# Kayan22v1.net
KiCad netlist of a schematic drawn in Altium Designer
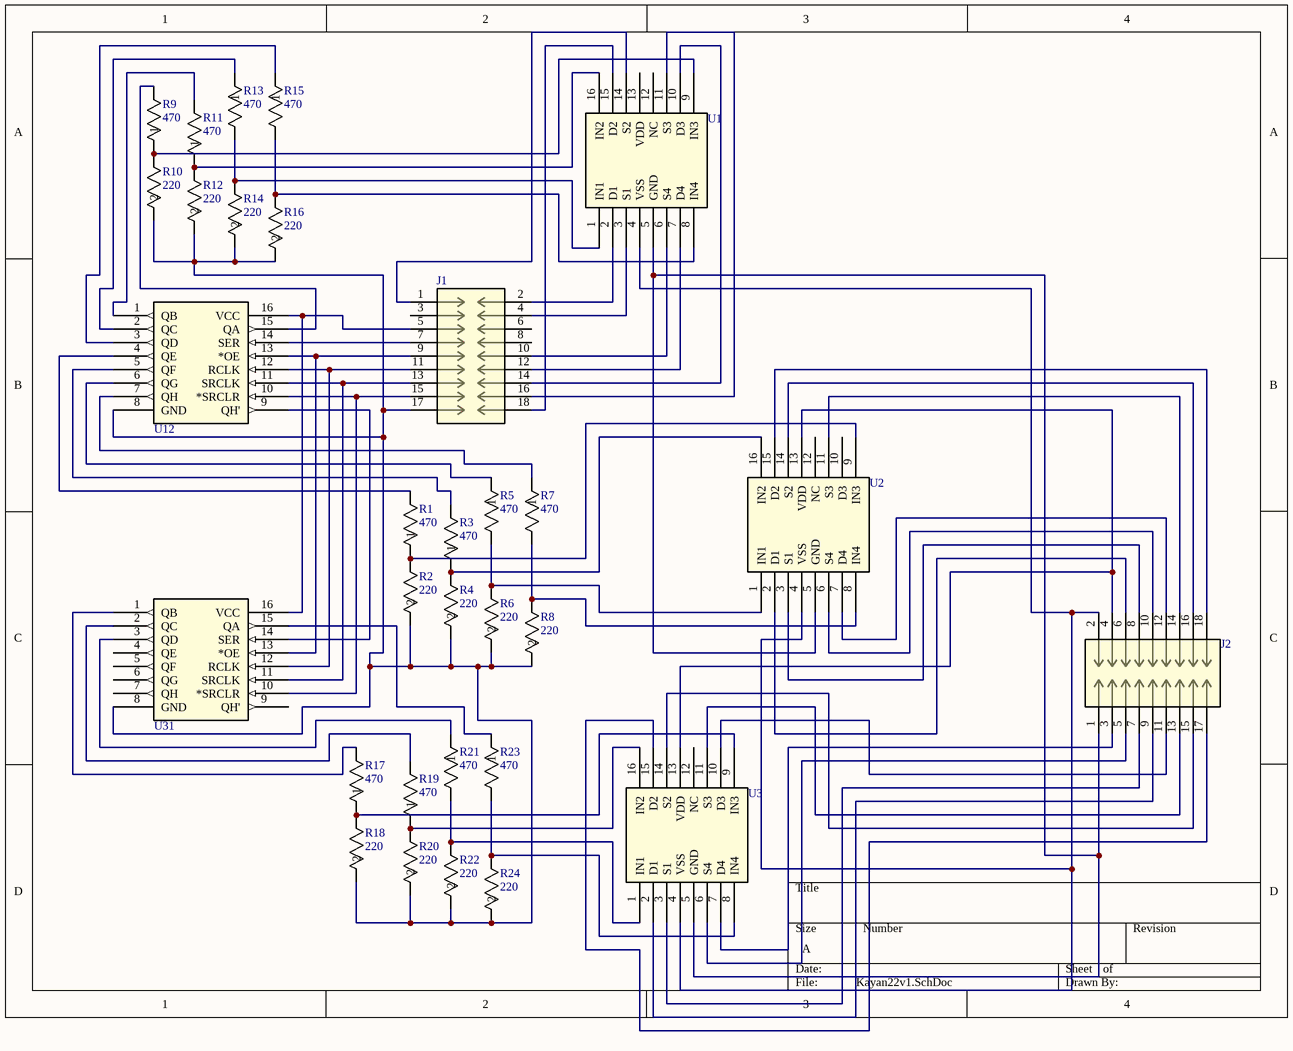
[diagram p0: Kayan22v1.SchDoc]

(export (version "E")
  (design (tool "Eeschema 10.0.6"))
  (components
    (comp (ref "J1")
      (value "68602-116HLF")
      (footprint "CONN_68602-116HLF_AMP")
      (description "No Description Available")
      (fields (field (name "COPYRIGHT") "Copyright (C) 2023 Ultra Librarian. All rights reserved."))
      (libsource (lib "68602-116HLF") (part "68602-116HLF"))
    )
    (comp (ref "J2")
      (value "68602-116HLF")
      (footprint "CONN_68602-116HLF_AMP")
      (description "No Description Available")
      (fields (field (name "COPYRIGHT") "Copyright (C) 2023 Ultra Librarian. All rights reserved."))
      (libsource (lib "68602-116HLF") (part "68602-116HLF"))
    )
    (comp (ref "R1")
      (value "470")
      (footprint "RES_ERA6V,6K_PAN")
      (description "No Description Available")
      (fields
        (field (name "MANUFACTURER_PART_NUMBER") "ERA-6VEB4700V")
        (field (name "COPYRIGHT") "Copyright (C) 2023 Ultra Librarian. All rights reserved.")
      )
      (libsource (lib "ERA-6VEB4700V") (part "ERA-6VEB4700V"))
    )
    (comp (ref "R2")
      (value "220")
      (footprint "RC0805N_PAN")
      (description "No Description Available")
      (fields
        (field (name "MANUFACTURER_PART_NUMBER") "ERA-6AEB221V")
        (field (name "COPYRIGHT") "Copyright (C) 2023 Ultra Librarian. All rights reserved.")
      )
      (libsource (lib "ERA-6AEB221V") (part "ERA-6AEB221V"))
    )
    (comp (ref "R3")
      (value "470")
      (footprint "RES_ERA6V,6K_PAN")
      (description "No Description Available")
      (fields
        (field (name "MANUFACTURER_PART_NUMBER") "ERA-6VEB4700V")
        (field (name "COPYRIGHT") "Copyright (C) 2023 Ultra Librarian. All rights reserved.")
      )
      (libsource (lib "ERA-6VEB4700V") (part "ERA-6VEB4700V"))
    )
    (comp (ref "R4")
      (value "220")
      (footprint "RC0805N_PAN")
      (description "No Description Available")
      (fields
        (field (name "MANUFACTURER_PART_NUMBER") "ERA-6AEB221V")
        (field (name "COPYRIGHT") "Copyright (C) 2023 Ultra Librarian. All rights reserved.")
      )
      (libsource (lib "ERA-6AEB221V") (part "ERA-6AEB221V"))
    )
    (comp (ref "R5")
      (value "470")
      (footprint "RES_ERA6V,6K_PAN")
      (description "No Description Available")
      (fields
        (field (name "MANUFACTURER_PART_NUMBER") "ERA-6VEB4700V")
        (field (name "COPYRIGHT") "Copyright (C) 2023 Ultra Librarian. All rights reserved.")
      )
      (libsource (lib "ERA-6VEB4700V") (part "ERA-6VEB4700V"))
    )
    (comp (ref "R6")
      (value "220")
      (footprint "RC0805N_PAN")
      (description "No Description Available")
      (fields
        (field (name "MANUFACTURER_PART_NUMBER") "ERA-6AEB221V")
        (field (name "COPYRIGHT") "Copyright (C) 2023 Ultra Librarian. All rights reserved.")
      )
      (libsource (lib "ERA-6AEB221V") (part "ERA-6AEB221V"))
    )
    (comp (ref "R7")
      (value "470")
      (footprint "RES_ERA6V,6K_PAN")
      (description "No Description Available")
      (fields
        (field (name "MANUFACTURER_PART_NUMBER") "ERA-6VEB4700V")
        (field (name "COPYRIGHT") "Copyright (C) 2023 Ultra Librarian. All rights reserved.")
      )
      (libsource (lib "ERA-6VEB4700V") (part "ERA-6VEB4700V"))
    )
    (comp (ref "R8")
      (value "220")
      (footprint "RC0805N_PAN")
      (description "No Description Available")
      (fields
        (field (name "MANUFACTURER_PART_NUMBER") "ERA-6AEB221V")
        (field (name "COPYRIGHT") "Copyright (C) 2023 Ultra Librarian. All rights reserved.")
      )
      (libsource (lib "ERA-6AEB221V") (part "ERA-6AEB221V"))
    )
    (comp (ref "R9")
      (value "470")
      (footprint "RES_ERA6V,6K_PAN")
      (description "No Description Available")
      (fields
        (field (name "MANUFACTURER_PART_NUMBER") "ERA-6VEB4700V")
        (field (name "COPYRIGHT") "Copyright (C) 2023 Ultra Librarian. All rights reserved.")
      )
      (libsource (lib "ERA-6VEB4700V") (part "ERA-6VEB4700V"))
    )
    (comp (ref "R10")
      (value "220")
      (footprint "RC0805N_PAN")
      (description "No Description Available")
      (fields
        (field (name "MANUFACTURER_PART_NUMBER") "ERA-6AEB221V")
        (field (name "COPYRIGHT") "Copyright (C) 2023 Ultra Librarian. All rights reserved.")
      )
      (libsource (lib "ERA-6AEB221V") (part "ERA-6AEB221V"))
    )
    (comp (ref "R11")
      (value "470")
      (footprint "RES_ERA6V,6K_PAN")
      (description "No Description Available")
      (fields
        (field (name "MANUFACTURER_PART_NUMBER") "ERA-6VEB4700V")
        (field (name "COPYRIGHT") "Copyright (C) 2023 Ultra Librarian. All rights reserved.")
      )
      (libsource (lib "ERA-6VEB4700V") (part "ERA-6VEB4700V"))
    )
    (comp (ref "R12")
      (value "220")
      (footprint "RC0805N_PAN")
      (description "No Description Available")
      (fields
        (field (name "MANUFACTURER_PART_NUMBER") "ERA-6AEB221V")
        (field (name "COPYRIGHT") "Copyright (C) 2023 Ultra Librarian. All rights reserved.")
      )
      (libsource (lib "ERA-6AEB221V") (part "ERA-6AEB221V"))
    )
    (comp (ref "R13")
      (value "470")
      (footprint "RES_ERA6V,6K_PAN")
      (description "No Description Available")
      (fields
        (field (name "MANUFACTURER_PART_NUMBER") "ERA-6VEB4700V")
        (field (name "COPYRIGHT") "Copyright (C) 2023 Ultra Librarian. All rights reserved.")
      )
      (libsource (lib "ERA-6VEB4700V") (part "ERA-6VEB4700V"))
    )
    (comp (ref "R14")
      (value "220")
      (footprint "RC0805N_PAN")
      (description "No Description Available")
      (fields
        (field (name "MANUFACTURER_PART_NUMBER") "ERA-6AEB221V")
        (field (name "COPYRIGHT") "Copyright (C) 2023 Ultra Librarian. All rights reserved.")
      )
      (libsource (lib "ERA-6AEB221V") (part "ERA-6AEB221V"))
    )
    (comp (ref "R15")
      (value "470")
      (footprint "RES_ERA6V,6K_PAN")
      (description "No Description Available")
      (fields
        (field (name "MANUFACTURER_PART_NUMBER") "ERA-6VEB4700V")
        (field (name "COPYRIGHT") "Copyright (C) 2023 Ultra Librarian. All rights reserved.")
      )
      (libsource (lib "ERA-6VEB4700V") (part "ERA-6VEB4700V"))
    )
    (comp (ref "R16")
      (value "220")
      (footprint "RC0805N_PAN")
      (description "No Description Available")
      (fields
        (field (name "MANUFACTURER_PART_NUMBER") "ERA-6AEB221V")
        (field (name "COPYRIGHT") "Copyright (C) 2023 Ultra Librarian. All rights reserved.")
      )
      (libsource (lib "ERA-6AEB221V") (part "ERA-6AEB221V"))
    )
    (comp (ref "R17")
      (value "470")
      (footprint "RES_ERA6V,6K_PAN")
      (description "No Description Available")
      (fields
        (field (name "MANUFACTURER_PART_NUMBER") "ERA-6VEB4700V")
        (field (name "COPYRIGHT") "Copyright (C) 2023 Ultra Librarian. All rights reserved.")
      )
      (libsource (lib "ERA-6VEB4700V") (part "ERA-6VEB4700V"))
    )
    (comp (ref "R18")
      (value "220")
      (footprint "RC0805N_PAN")
      (description "No Description Available")
      (fields
        (field (name "MANUFACTURER_PART_NUMBER") "ERA-6AEB221V")
        (field (name "COPYRIGHT") "Copyright (C) 2023 Ultra Librarian. All rights reserved.")
      )
      (libsource (lib "ERA-6AEB221V") (part "ERA-6AEB221V"))
    )
    (comp (ref "R19")
      (value "470")
      (footprint "RES_ERA6V,6K_PAN")
      (description "No Description Available")
      (fields
        (field (name "MANUFACTURER_PART_NUMBER") "ERA-6VEB4700V")
        (field (name "COPYRIGHT") "Copyright (C) 2023 Ultra Librarian. All rights reserved.")
      )
      (libsource (lib "ERA-6VEB4700V") (part "ERA-6VEB4700V"))
    )
    (comp (ref "R20")
      (value "220")
      (footprint "RC0805N_PAN")
      (description "No Description Available")
      (fields
        (field (name "MANUFACTURER_PART_NUMBER") "ERA-6AEB221V")
        (field (name "COPYRIGHT") "Copyright (C) 2023 Ultra Librarian. All rights reserved.")
      )
      (libsource (lib "ERA-6AEB221V") (part "ERA-6AEB221V"))
    )
    (comp (ref "R21")
      (value "470")
      (footprint "RES_ERA6V,6K_PAN")
      (description "No Description Available")
      (fields
        (field (name "MANUFACTURER_PART_NUMBER") "ERA-6VEB4700V")
        (field (name "COPYRIGHT") "Copyright (C) 2023 Ultra Librarian. All rights reserved.")
      )
      (libsource (lib "ERA-6VEB4700V") (part "ERA-6VEB4700V"))
    )
    (comp (ref "R22")
      (value "220")
      (footprint "RC0805N_PAN")
      (description "No Description Available")
      (fields
        (field (name "MANUFACTURER_PART_NUMBER") "ERA-6AEB221V")
        (field (name "COPYRIGHT") "Copyright (C) 2023 Ultra Librarian. All rights reserved.")
      )
      (libsource (lib "ERA-6AEB221V") (part "ERA-6AEB221V"))
    )
    (comp (ref "R23")
      (value "470")
      (footprint "RES_ERA6V,6K_PAN")
      (description "No Description Available")
      (fields
        (field (name "MANUFACTURER_PART_NUMBER") "ERA-6VEB4700V")
        (field (name "COPYRIGHT") "Copyright (C) 2023 Ultra Librarian. All rights reserved.")
      )
      (libsource (lib "ERA-6VEB4700V") (part "ERA-6VEB4700V"))
    )
    (comp (ref "R24")
      (value "220")
      (footprint "RC0805N_PAN")
      (description "No Description Available")
      (fields
        (field (name "MANUFACTURER_PART_NUMBER") "ERA-6AEB221V")
        (field (name "COPYRIGHT") "Copyright (C) 2023 Ultra Librarian. All rights reserved.")
      )
      (libsource (lib "ERA-6AEB221V") (part "ERA-6AEB221V"))
    )
    (comp (ref "U1")
      (value "ADG1412YRUZ-REEL7")
      (footprint "RU_16_ADI")
      (description "No Description Available")
      (fields (field (name "COPYRIGHT") "Copyright (C) 2023 Ultra Librarian. All rights reserved."))
      (libsource (lib "ADG1412YRUZ-REEL7") (part "ADG1412YRUZ-REEL7"))
    )
    (comp (ref "U2")
      (value "ADG1412YRUZ-REEL7")
      (footprint "RU_16_ADI")
      (description "No Description Available")
      (fields (field (name "COPYRIGHT") "Copyright (C) 2023 Ultra Librarian. All rights reserved."))
      (libsource (lib "ADG1412YRUZ-REEL7") (part "ADG1412YRUZ-REEL7"))
    )
    (comp (ref "U3")
      (value "ADG1412YRUZ-REEL7")
      (footprint "RU_16_ADI")
      (description "No Description Available")
      (fields (field (name "COPYRIGHT") "Copyright (C) 2023 Ultra Librarian. All rights reserved."))
      (libsource (lib "ADG1412YRUZ-REEL7") (part "ADG1412YRUZ-REEL7"))
    )
    (comp (ref "U12")
      (value "SN74HC595DWR")
      (footprint "DW16")
      (description "No Description Available")
      (fields (field (name "COPYRIGHT") "Copyright (C) 2023 Ultra Librarian. All rights reserved."))
      (libsource (lib "SN74HC595DWR") (part "SN74HC595DWR"))
    )
    (comp (ref "U31")
      (value "SN74HC595DWR")
      (footprint "DW16")
      (description "No Description Available")
      (fields (field (name "COPYRIGHT") "Copyright (C) 2023 Ultra Librarian. All rights reserved."))
      (libsource (lib "SN74HC595DWR") (part "SN74HC595DWR"))
    )
  )
  (nets
    (net (code "1") (name "Net-(U1-D1)") (class "Default")
      (node (ref "J1") (pin "2") (pinfunction "2_2") (pintype "passive"))
      (node (ref "U1") (pin "2") (pinfunction "D1_2") (pintype "passive"))
    )
    (net (code "2") (name "Net-(U1-D2)") (class "Default")
      (node (ref "J1") (pin "18") (pinfunction "18_18") (pintype "passive"))
      (node (ref "U1") (pin "15") (pinfunction "D2_15") (pintype "passive"))
    )
    (net (code "3") (name "Net-(U1-D3)") (class "Default")
      (node (ref "J1") (pin "14") (pinfunction "14_14") (pintype "passive"))
      (node (ref "U1") (pin "10") (pinfunction "D3_10") (pintype "passive"))
    )
    (net (code "4") (name "Net-(U1-D4)") (class "Default")
      (node (ref "J1") (pin "12") (pinfunction "12_12") (pintype "passive"))
      (node (ref "U1") (pin "7") (pinfunction "D4_7") (pintype "passive"))
    )
    (net (code "5") (name "Net-(U1-GND)") (class "Default")
      (node (ref "J2") (pin "1") (pinfunction "1_1") (pintype "passive"))
      (node (ref "U1") (pin "5") (pinfunction "GND_5") (pintype "passive"))
      (node (ref "U2") (pin "5") (pinfunction "GND_5") (pintype "passive"))
      (node (ref "U3") (pin "5") (pinfunction "GND_5") (pintype "passive"))
    )
    (net (code "6") (name "Net-(U1-IN1)") (class "Default")
      (node (ref "R13") (pin "2") (pinfunction "2_2") (pintype "passive"))
      (node (ref "R14") (pin "1") (pinfunction "1_1") (pintype "passive"))
      (node (ref "U1") (pin "1") (pinfunction "IN1_1") (pintype "passive"))
    )
    (net (code "7") (name "Net-(U1-IN2)") (class "Default")
      (node (ref "R11") (pin "1") (pinfunction "1_1") (pintype "passive"))
      (node (ref "R12") (pin "1") (pinfunction "1_1") (pintype "passive"))
      (node (ref "U1") (pin "16") (pinfunction "IN2_16") (pintype "passive"))
    )
    (net (code "8") (name "Net-(U1-IN3)") (class "Default")
      (node (ref "R10") (pin "1") (pinfunction "1_1") (pintype "passive"))
      (node (ref "R9") (pin "1") (pinfunction "1_1") (pintype "passive"))
      (node (ref "U1") (pin "9") (pinfunction "IN3_9") (pintype "passive"))
    )
    (net (code "9") (name "Net-(U1-IN4)") (class "Default")
      (node (ref "R15") (pin "2") (pinfunction "2_2") (pintype "passive"))
      (node (ref "R16") (pin "1") (pinfunction "1_1") (pintype "passive"))
      (node (ref "U1") (pin "8") (pinfunction "IN4_8") (pintype "passive"))
    )
    (net (code "10") (name "Net-(U1-S1)") (class "Default")
      (node (ref "J1") (pin "4") (pinfunction "4_4") (pintype "passive"))
      (node (ref "U1") (pin "3") (pinfunction "S1_3") (pintype "passive"))
    )
    (net (code "11") (name "Net-(U1-S2)") (class "Default")
      (node (ref "J1") (pin "1") (pinfunction "1_1") (pintype "passive"))
      (node (ref "U1") (pin "14") (pinfunction "S2_14") (pintype "passive"))
    )
    (net (code "12") (name "Net-(U1-S3)") (class "Default")
      (node (ref "J1") (pin "16") (pinfunction "16_16") (pintype "passive"))
      (node (ref "U1") (pin "11") (pinfunction "S3_11") (pintype "passive"))
    )
    (net (code "13") (name "Net-(U1-S4)") (class "Default")
      (node (ref "J1") (pin "10") (pinfunction "10_10") (pintype "passive"))
      (node (ref "U1") (pin "6") (pinfunction "S4_6") (pintype "passive"))
    )
    (net (code "14") (name "Net-(U1-VSS)") (class "Default")
      (node (ref "J2") (pin "2") (pinfunction "2_2") (pintype "passive"))
      (node (ref "U1") (pin "4") (pinfunction "VSS_4") (pintype "passive"))
      (node (ref "U2") (pin "4") (pinfunction "VSS_4") (pintype "passive"))
      (node (ref "U3") (pin "4") (pinfunction "VSS_4") (pintype "passive"))
    )
    (net (code "15") (name "Net-(U2-D1)") (class "Default")
      (node (ref "J2") (pin "6") (pinfunction "6_6") (pintype "passive"))
      (node (ref "U2") (pin "2") (pinfunction "D1_2") (pintype "passive"))
    )
    (net (code "16") (name "Net-(U2-D2)") (class "Default")
      (node (ref "J2") (pin "18") (pinfunction "18_18") (pintype "passive"))
      (node (ref "U2") (pin "15") (pinfunction "D2_15") (pintype "passive"))
    )
    (net (code "17") (name "Net-(U2-D4)") (class "Default")
      (node (ref "J2") (pin "12") (pinfunction "12_12") (pintype "passive"))
      (node (ref "U2") (pin "7") (pinfunction "D4_7") (pintype "passive"))
    )
    (net (code "18") (name "Net-(U2-IN1)") (class "Default")
      (node (ref "R5") (pin "2") (pinfunction "2_2") (pintype "passive"))
      (node (ref "R6") (pin "1") (pinfunction "1_1") (pintype "passive"))
      (node (ref "U2") (pin "1") (pinfunction "IN1_1") (pintype "passive"))
    )
    (net (code "19") (name "Net-(U2-IN2)") (class "Default")
      (node (ref "R3") (pin "1") (pinfunction "1_1") (pintype "passive"))
      (node (ref "R4") (pin "1") (pinfunction "1_1") (pintype "passive"))
      (node (ref "U2") (pin "16") (pinfunction "IN2_16") (pintype "passive"))
    )
    (net (code "20") (name "Net-(U2-IN3)") (class "Default")
      (node (ref "R1") (pin "1") (pinfunction "1_1") (pintype "passive"))
      (node (ref "R2") (pin "1") (pinfunction "1_1") (pintype "passive"))
      (node (ref "U2") (pin "9") (pinfunction "IN3_9") (pintype "passive"))
    )
    (net (code "21") (name "Net-(U2-IN4)") (class "Default")
      (node (ref "R7") (pin "2") (pinfunction "2_2") (pintype "passive"))
      (node (ref "R8") (pin "1") (pinfunction "1_1") (pintype "passive"))
      (node (ref "U2") (pin "8") (pinfunction "IN4_8") (pintype "passive"))
    )
    (net (code "22") (name "Net-(U2-S1)") (class "Default")
      (node (ref "J2") (pin "8") (pinfunction "8_8") (pintype "passive"))
      (node (ref "U2") (pin "3") (pinfunction "S1_3") (pintype "passive"))
    )
    (net (code "23") (name "Net-(U2-S2)") (class "Default")
      (node (ref "J2") (pin "16") (pinfunction "16_16") (pintype "passive"))
      (node (ref "U2") (pin "14") (pinfunction "S2_14") (pintype "passive"))
    )
    (net (code "24") (name "Net-(U2-S3)") (class "Default")
      (node (ref "J2") (pin "14") (pinfunction "14_14") (pintype "passive"))
      (node (ref "U2") (pin "11") (pinfunction "S3_11") (pintype "passive"))
    )
    (net (code "25") (name "Net-(U2-S4)") (class "Default")
      (node (ref "J2") (pin "10") (pinfunction "10_10") (pintype "passive"))
      (node (ref "U2") (pin "6") (pinfunction "S4_6") (pintype "passive"))
    )
    (net (code "26") (name "Net-(U2-VDD)") (class "Default")
      (node (ref "J2") (pin "4") (pinfunction "4_4") (pintype "passive"))
      (node (ref "U2") (pin "13") (pinfunction "VDD_13") (pintype "power_in"))
      (node (ref "U3") (pin "13") (pinfunction "VDD_13") (pintype "power_in"))
    )
    (net (code "27") (name "Net-(U3-D1)") (class "Default")
      (node (ref "J2") (pin "9") (pinfunction "9_9") (pintype "passive"))
      (node (ref "U3") (pin "2") (pinfunction "D1_2") (pintype "passive"))
    )
    (net (code "28") (name "Net-(U3-D2)") (class "Default")
      (node (ref "J2") (pin "17") (pinfunction "17_17") (pintype "passive"))
      (node (ref "U3") (pin "15") (pinfunction "D2_15") (pintype "passive"))
    )
    (net (code "29") (name "Net-(U3-D3)") (class "Default")
      (node (ref "J2") (pin "11") (pinfunction "11_11") (pintype "passive"))
      (node (ref "U3") (pin "10") (pinfunction "D3_10") (pintype "passive"))
    )
    (net (code "30") (name "Net-(U3-D4)") (class "Default")
      (node (ref "J2") (pin "3") (pinfunction "3_3") (pintype "passive"))
      (node (ref "U3") (pin "7") (pinfunction "D4_7") (pintype "passive"))
    )
    (net (code "31") (name "Net-(U3-IN1)") (class "Default")
      (node (ref "R21") (pin "2") (pinfunction "2_2") (pintype "passive"))
      (node (ref "R22") (pin "1") (pinfunction "1_1") (pintype "passive"))
      (node (ref "U3") (pin "1") (pinfunction "IN1_1") (pintype "passive"))
    )
    (net (code "32") (name "Net-(U3-IN2)") (class "Default")
      (node (ref "R19") (pin "1") (pinfunction "1_1") (pintype "passive"))
      (node (ref "R20") (pin "1") (pinfunction "1_1") (pintype "passive"))
      (node (ref "U3") (pin "16") (pinfunction "IN2_16") (pintype "passive"))
    )
    (net (code "33") (name "Net-(U3-IN3)") (class "Default")
      (node (ref "R17") (pin "1") (pinfunction "1_1") (pintype "passive"))
      (node (ref "R18") (pin "1") (pinfunction "1_1") (pintype "passive"))
      (node (ref "U3") (pin "9") (pinfunction "IN3_9") (pintype "passive"))
    )
    (net (code "34") (name "Net-(U3-IN4)") (class "Default")
      (node (ref "R23") (pin "2") (pinfunction "2_2") (pintype "passive"))
      (node (ref "R24") (pin "1") (pinfunction "1_1") (pintype "passive"))
      (node (ref "U3") (pin "8") (pinfunction "IN4_8") (pintype "passive"))
    )
    (net (code "35") (name "Net-(U3-S1)") (class "Default")
      (node (ref "J2") (pin "7") (pinfunction "7_7") (pintype "passive"))
      (node (ref "U3") (pin "3") (pinfunction "S1_3") (pintype "passive"))
    )
    (net (code "36") (name "Net-(U3-S2)") (class "Default")
      (node (ref "J2") (pin "15") (pinfunction "15_15") (pintype "passive"))
      (node (ref "U3") (pin "14") (pinfunction "S2_14") (pintype "passive"))
    )
    (net (code "37") (name "Net-(U3-S3)") (class "Default")
      (node (ref "J2") (pin "13") (pinfunction "13_13") (pintype "passive"))
      (node (ref "U3") (pin "11") (pinfunction "S3_11") (pintype "passive"))
    )
    (net (code "38") (name "Net-(U3-S4)") (class "Default")
      (node (ref "J2") (pin "5") (pinfunction "5_5") (pintype "passive"))
      (node (ref "U3") (pin "6") (pinfunction "S4_6") (pintype "passive"))
    )
    (net (code "39") (name "Net-(U12-*OE)") (class "Default")
      (node (ref "J1") (pin "9") (pinfunction "9_9") (pintype "passive"))
      (node (ref "U12") (pin "13") (pinfunction "*OE_13") (pintype "input"))
      (node (ref "U31") (pin "13") (pinfunction "*OE_13") (pintype "input"))
    )
    (net (code "40") (name "Net-(U12-*SRCLR)") (class "Default")
      (node (ref "J1") (pin "15") (pinfunction "15_15") (pintype "passive"))
      (node (ref "U12") (pin "10") (pinfunction "*SRCLR_10") (pintype "input"))
      (node (ref "U31") (pin "10") (pinfunction "*SRCLR_10") (pintype "input"))
    )
    (net (code "41") (name "Net-(U12-GND)") (class "Default")
      (node (ref "J1") (pin "17") (pinfunction "17_17") (pintype "passive"))
      (node (ref "R10") (pin "2") (pinfunction "2_2") (pintype "passive"))
      (node (ref "R12") (pin "2") (pinfunction "2_2") (pintype "passive"))
      (node (ref "R14") (pin "2") (pinfunction "2_2") (pintype "passive"))
      (node (ref "R16") (pin "2") (pinfunction "2_2") (pintype "passive"))
      (node (ref "R18") (pin "2") (pinfunction "2_2") (pintype "passive"))
      (node (ref "R2") (pin "2") (pinfunction "2_2") (pintype "passive"))
      (node (ref "R20") (pin "2") (pinfunction "2_2") (pintype "passive"))
      (node (ref "R22") (pin "2") (pinfunction "2_2") (pintype "passive"))
      (node (ref "R24") (pin "2") (pinfunction "2_2") (pintype "passive"))
      (node (ref "R4") (pin "2") (pinfunction "2_2") (pintype "passive"))
      (node (ref "R6") (pin "2") (pinfunction "2_2") (pintype "passive"))
      (node (ref "R8") (pin "2") (pinfunction "2_2") (pintype "passive"))
      (node (ref "U12") (pin "8") (pinfunction "GND_8") (pintype "power_in"))
      (node (ref "U31") (pin "8") (pinfunction "GND_8") (pintype "power_in"))
    )
    (net (code "42") (name "Net-(U12-QA)") (class "Default")
      (node (ref "R9") (pin "2") (pinfunction "2_2") (pintype "passive"))
      (node (ref "U12") (pin "15") (pinfunction "QA_15") (pintype "output"))
    )
    (net (code "43") (name "Net-(U12-QB)") (class "Default")
      (node (ref "R11") (pin "2") (pinfunction "2_2") (pintype "passive"))
      (node (ref "U12") (pin "1") (pinfunction "QB_1") (pintype "output"))
    )
    (net (code "44") (name "Net-(U12-QC)") (class "Default")
      (node (ref "R13") (pin "1") (pinfunction "1_1") (pintype "passive"))
      (node (ref "U12") (pin "2") (pinfunction "QC_2") (pintype "output"))
    )
    (net (code "45") (name "Net-(U12-QD)") (class "Default")
      (node (ref "R15") (pin "1") (pinfunction "1_1") (pintype "passive"))
      (node (ref "U12") (pin "3") (pinfunction "QD_3") (pintype "output"))
    )
    (net (code "46") (name "Net-(U12-QE)") (class "Default")
      (node (ref "R1") (pin "2") (pinfunction "2_2") (pintype "passive"))
      (node (ref "U12") (pin "4") (pinfunction "QE_4") (pintype "output"))
    )
    (net (code "47") (name "Net-(U12-QF)") (class "Default")
      (node (ref "R3") (pin "2") (pinfunction "2_2") (pintype "passive"))
      (node (ref "U12") (pin "5") (pinfunction "QF_5") (pintype "output"))
    )
    (net (code "48") (name "Net-(U12-QG)") (class "Default")
      (node (ref "R5") (pin "1") (pinfunction "1_1") (pintype "passive"))
      (node (ref "U12") (pin "6") (pinfunction "QG_6") (pintype "output"))
    )
    (net (code "49") (name "Net-(U12-QH')") (class "Default")
      (node (ref "U12") (pin "9") (pinfunction "QH'_9") (pintype "output"))
      (node (ref "U31") (pin "14") (pinfunction "SER_14") (pintype "input"))
    )
    (net (code "50") (name "Net-(U12-QH)") (class "Default")
      (node (ref "R7") (pin "1") (pinfunction "1_1") (pintype "passive"))
      (node (ref "U12") (pin "7") (pinfunction "QH_7") (pintype "output"))
    )
    (net (code "51") (name "Net-(U12-RCLK)") (class "Default")
      (node (ref "J1") (pin "11") (pinfunction "11_11") (pintype "passive"))
      (node (ref "U12") (pin "12") (pinfunction "RCLK_12") (pintype "input"))
      (node (ref "U31") (pin "12") (pinfunction "RCLK_12") (pintype "input"))
    )
    (net (code "52") (name "Net-(U12-SER)") (class "Default")
      (node (ref "J1") (pin "7") (pinfunction "7_7") (pintype "passive"))
      (node (ref "U12") (pin "14") (pinfunction "SER_14") (pintype "input"))
    )
    (net (code "53") (name "Net-(U12-SRCLK)") (class "Default")
      (node (ref "J1") (pin "13") (pinfunction "13_13") (pintype "passive"))
      (node (ref "U12") (pin "11") (pinfunction "SRCLK_11") (pintype "input"))
      (node (ref "U31") (pin "11") (pinfunction "SRCLK_11") (pintype "input"))
    )
    (net (code "54") (name "Net-(U12-VCC)") (class "Default")
      (node (ref "J1") (pin "5") (pinfunction "5_5") (pintype "passive"))
      (node (ref "U12") (pin "16") (pinfunction "VCC_16") (pintype "power_in"))
      (node (ref "U31") (pin "16") (pinfunction "VCC_16") (pintype "power_in"))
    )
    (net (code "55") (name "Net-(U31-QA)") (class "Default")
      (node (ref "R23") (pin "1") (pinfunction "1_1") (pintype "passive"))
      (node (ref "U31") (pin "15") (pinfunction "QA_15") (pintype "output"))
    )
    (net (code "56") (name "Net-(U31-QB)") (class "Default")
      (node (ref "R17") (pin "2") (pinfunction "2_2") (pintype "passive"))
      (node (ref "U31") (pin "1") (pinfunction "QB_1") (pintype "output"))
    )
    (net (code "57") (name "Net-(U31-QC)") (class "Default")
      (node (ref "R19") (pin "2") (pinfunction "2_2") (pintype "passive"))
      (node (ref "U31") (pin "2") (pinfunction "QC_2") (pintype "output"))
    )
    (net (code "58") (name "Net-(U31-QD)") (class "Default")
      (node (ref "R21") (pin "1") (pinfunction "1_1") (pintype "passive"))
      (node (ref "U31") (pin "3") (pinfunction "QD_3") (pintype "output"))
    )
    (net (code "59") (name "unconnected-(J1-Pad3)") (class "Default")
      (node (ref "J1") (pin "3") (pinfunction "3_3") (pintype "passive"))
    )
    (net (code "60") (name "unconnected-(J1-Pad6)") (class "Default")
      (node (ref "J1") (pin "6") (pinfunction "6_6") (pintype "passive"))
    )
    (net (code "61") (name "unconnected-(J1-Pad8)") (class "Default")
      (node (ref "J1") (pin "8") (pinfunction "8_8") (pintype "passive"))
    )
    (net (code "62") (name "unconnected-(U1-NC-Pad12)") (class "Default")
      (node (ref "U1") (pin "12") (pinfunction "NC_12") (pintype "passive"))
    )
    (net (code "63") (name "unconnected-(U1-VDD-Pad13)") (class "Default")
      (node (ref "U1") (pin "13") (pinfunction "VDD_13") (pintype "power_in"))
    )
    (net (code "64") (name "unconnected-(U2-D3-Pad10)") (class "Default")
      (node (ref "U2") (pin "10") (pinfunction "D3_10") (pintype "passive"))
    )
    (net (code "65") (name "unconnected-(U2-NC-Pad12)") (class "Default")
      (node (ref "U2") (pin "12") (pinfunction "NC_12") (pintype "passive"))
    )
    (net (code "66") (name "unconnected-(U3-NC-Pad12)") (class "Default")
      (node (ref "U3") (pin "12") (pinfunction "NC_12") (pintype "passive"))
    )
    (net (code "67") (name "unconnected-(U31-QE-Pad4)") (class "Default")
      (node (ref "U31") (pin "4") (pinfunction "QE_4") (pintype "output"))
    )
    (net (code "68") (name "unconnected-(U31-QF-Pad5)") (class "Default")
      (node (ref "U31") (pin "5") (pinfunction "QF_5") (pintype "output"))
    )
    (net (code "69") (name "unconnected-(U31-QG-Pad6)") (class "Default")
      (node (ref "U31") (pin "6") (pinfunction "QG_6") (pintype "output"))
    )
    (net (code "70") (name "unconnected-(U31-QH'-Pad9)") (class "Default")
      (node (ref "U31") (pin "9") (pinfunction "QH'_9") (pintype "output"))
    )
    (net (code "71") (name "unconnected-(U31-QH-Pad7)") (class "Default")
      (node (ref "U31") (pin "7") (pinfunction "QH_7") (pintype "output"))
    )
  )
)
